# Adapter.net
KiCad netlist of a schematic drawn in EAGLE
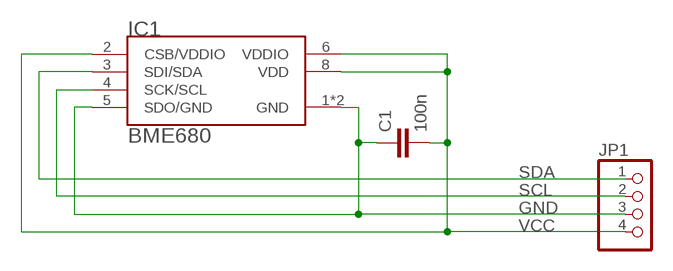
[diagram p0: schematic, sheet 1]

(export (version "E")
  (design (tool "Eeschema 10.0.6"))
  (components
    (comp (ref "C1")
      (value "100n")
      (footprint "eagle-import:C0805")
      (libsource (lib "eagle-import") (part "C-EUC0805"))
    )
    (comp (ref "IC1")
      (value "BME680")
      (footprint "eagle-import:LGA8")
      (libsource (lib "eagle-import") (part "BME680"))
    )
    (comp (ref "JP1")
      (value "PINHD-1X4")
      (footprint "eagle-import:1X04")
      (libsource (lib "eagle-import") (part "PINHD-1X4"))
    )
  )
  (nets
    (net (code "1") (name "/GND") (class "Default")
      (node (ref "C1") (pin "1") (pinfunction "1_1") (pintype "passive"))
      (node (ref "IC1") (pin "1") (pinfunction "GND_1") (pintype "power_in"))
      (node (ref "IC1") (pin "5") (pinfunction "SDO/GND_5") (pintype "bidirectional"))
      (node (ref "IC1") (pin "7") (pinfunction "GND_7") (pintype "power_in"))
      (node (ref "JP1") (pin "3") (pinfunction "3_3") (pintype "passive"))
    )
    (net (code "2") (name "/SCL") (class "Default")
      (node (ref "IC1") (pin "4") (pinfunction "SCK/SCL_4") (pintype "input"))
      (node (ref "JP1") (pin "2") (pinfunction "2_2") (pintype "passive"))
    )
    (net (code "3") (name "/SDA") (class "Default")
      (node (ref "IC1") (pin "3") (pinfunction "SDI/SDA_3") (pintype "bidirectional"))
      (node (ref "JP1") (pin "1") (pinfunction "1_1") (pintype "passive"))
    )
    (net (code "4") (name "/VCC") (class "Default")
      (node (ref "C1") (pin "2") (pinfunction "2_2") (pintype "passive"))
      (node (ref "IC1") (pin "2") (pinfunction "CSB/VDDIO_2") (pintype "input"))
      (node (ref "IC1") (pin "6") (pinfunction "VDDIO_6") (pintype "power_in"))
      (node (ref "IC1") (pin "8") (pinfunction "VDD_8") (pintype "power_in"))
      (node (ref "JP1") (pin "4") (pinfunction "4_4") (pintype "passive"))
    )
  )
)
